# RasPiTimePowerSW_WithSTTS751.net
KiCad netlist of a schematic drawn in EAGLE
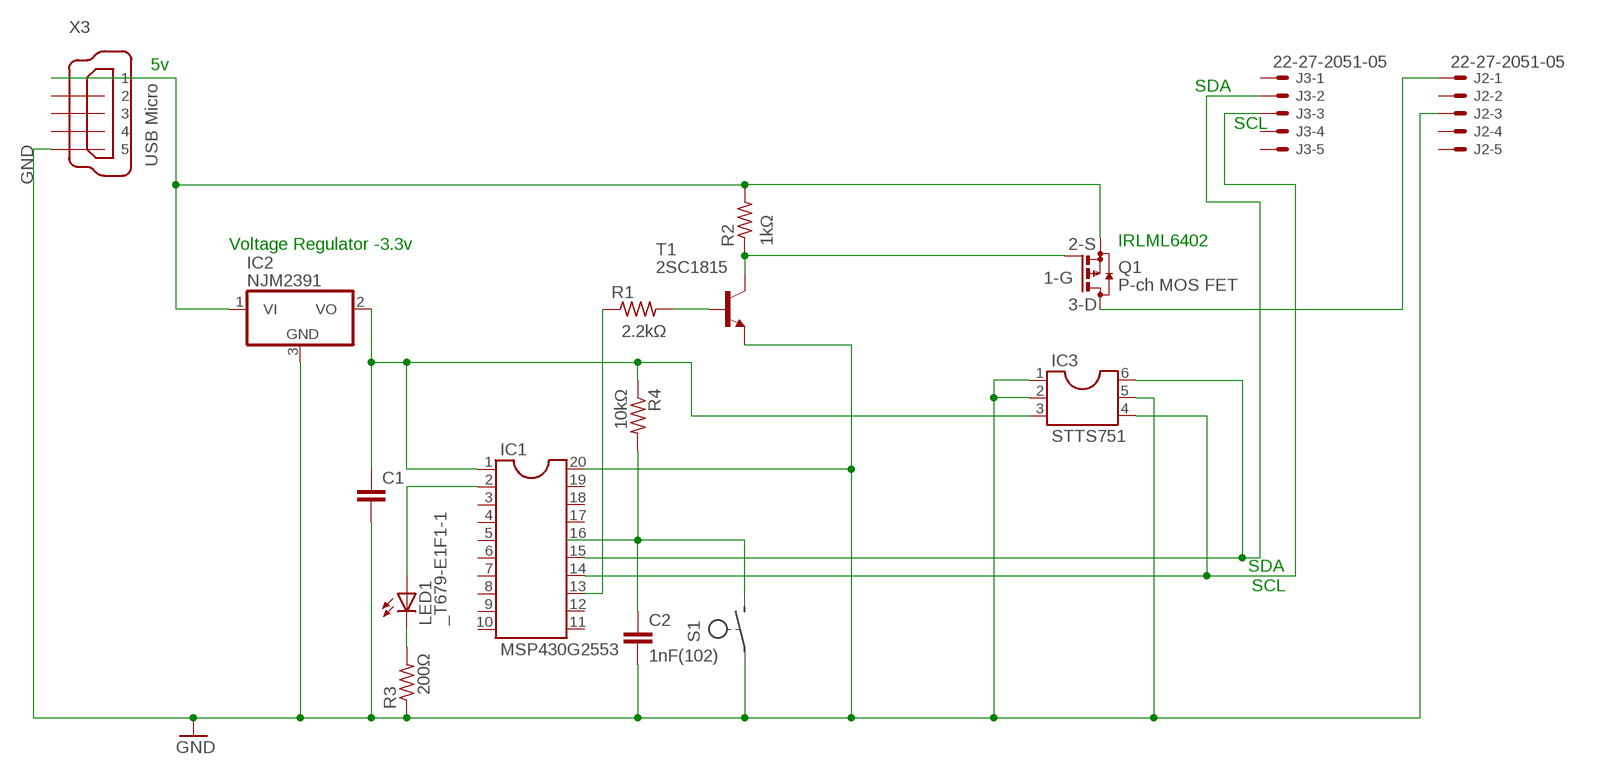
[diagram p0: schematic, sheet 1]

(export (version "E")
  (design (tool "Eeschema 10.0.6"))
  (components
    (comp (ref "C1")
      (value "C-EU075-042X103")
      (footprint "eagle-import:C075-042X103")
      (libsource (lib "eagle-import") (part "C-EU075-042X103"))
    )
    (comp (ref "C2")
      (value "1nF(102)")
      (footprint "eagle-import:C025-024X044")
      (libsource (lib "eagle-import") (part "C-EU025-024X044"))
    )
    (comp (ref "IC1")
      (value "MSP430G2553")
      (footprint "eagle-import:SOCKET-20")
      (libsource (lib "eagle-import") (part "DIL20S"))
    )
    (comp (ref "IC2")
      (value "NJM2391")
      (footprint "eagle-import:TO252")
      (libsource (lib "eagle-import") (part "78DT05"))
    )
    (comp (ref "IC3")
      (value "STTS751")
      (footprint "eagle-import:DIL06")
      (libsource (lib "eagle-import") (part "DIL6"))
    )
    (comp (ref "J2")
      (value "22-27-2051-05")
      (footprint "eagle-import:6410-05")
      (libsource (lib "eagle-import") (part "22-?-0527-2051"))
    )
    (comp (ref "J3")
      (value "22-27-2051-05")
      (footprint "eagle-import:6410-05")
      (libsource (lib "eagle-import") (part "22-?-0527-2051"))
    )
    (comp (ref "LED1")
      (value "_T679-E1F1-1")
      (footprint "eagle-import:PLCC2")
      (libsource (lib "eagle-import") (part "_T679-?-1E1F1LG"))
    )
    (comp (ref "Q1")
      (value "P-ch MOS FET")
      (footprint "eagle-import:SOT23")
      (libsource (lib "eagle-import") (part "BSS84"))
    )
    (comp (ref "R1")
      (value "R-US_M1206")
      (footprint "eagle-import:M1206")
      (fields (field (name "R") "2.2kΩ"))
      (libsource (lib "eagle-import") (part "R-US_M1206"))
    )
    (comp (ref "R2")
      (value "R-US_M1206")
      (footprint "eagle-import:M1206")
      (fields (field (name "1K") "1kΩ"))
      (libsource (lib "eagle-import") (part "R-US_M1206"))
    )
    (comp (ref "R3")
      (value "R-US_M1206")
      (footprint "eagle-import:M1206")
      (fields (field (name "R") "200Ω"))
      (libsource (lib "eagle-import") (part "R-US_M1206"))
    )
    (comp (ref "R4")
      (value "10kΩ")
      (footprint "eagle-import:M1206")
      (libsource (lib "eagle-import") (part "R-US_M1206"))
    )
    (comp (ref "T1")
      (value "2SC1815")
      (footprint "eagle-import:TO92-ECB")
      (libsource (lib "eagle-import") (part "2SC1815"))
    )
    (comp (ref "X3")
      (value "USB Micro")
      (footprint "eagle-import:32005-400")
      (libsource (lib "eagle-import") (part "MINI-USB_SHIELD5P4-32005-400"))
    )
  )
  (nets
    (net (code "1") (name "GND") (class "Default")
      (node (ref "C1") (pin "2") (pinfunction "2_2") (pintype "passive"))
      (node (ref "C2") (pin "2") (pinfunction "2_2") (pintype "passive"))
      (node (ref "IC1") (pin "20") (pinfunction "20_20") (pintype "passive"))
      (node (ref "IC2") (pin "3") (pinfunction "GND_3") (pintype "passive"))
      (node (ref "IC3") (pin "1") (pinfunction "1_1") (pintype "passive"))
      (node (ref "IC3") (pin "2") (pinfunction "2_2") (pintype "passive"))
      (node (ref "IC3") (pin "5") (pinfunction "5_5") (pintype "passive"))
      (node (ref "J2") (pin "3") (pinfunction "S_3") (pintype "passive"))
      (node (ref "R3") (pin "1") (pinfunction "1_1") (pintype "passive"))
      (node (ref "T1") (pin "E") (pinfunction "E_E") (pintype "passive"))
      (node (ref "X3") (pin "5") (pinfunction "5_5") (pintype "passive"))
    )
    (net (code "2") (name "Net-(C2-Pad1)") (class "Default")
      (node (ref "C2") (pin "1") (pinfunction "1_1") (pintype "passive"))
      (node (ref "R4") (pin "2") (pinfunction "2_2") (pintype "passive"))
    )
    (net (code "3") (name "Net-(IC1-Pad2)") (class "Default")
      (node (ref "IC1") (pin "2") (pinfunction "2_2") (pintype "passive"))
      (node (ref "LED1") (pin "A") (pinfunction "A_A") (pintype "passive"))
    )
    (net (code "4") (name "Net-(IC1-Pad13)") (class "Default")
      (node (ref "IC1") (pin "13") (pinfunction "13_13") (pintype "passive"))
      (node (ref "R1") (pin "1") (pinfunction "1_1") (pintype "passive"))
    )
    (net (code "5") (name "Net-(IC2-VI)") (class "Default")
      (node (ref "IC2") (pin "1") (pinfunction "VI_1") (pintype "input"))
      (node (ref "Q1") (pin "2") (pinfunction "S_2") (pintype "passive"))
      (node (ref "R2") (pin "2") (pinfunction "2_2") (pintype "passive"))
      (node (ref "X3") (pin "1") (pinfunction "1_1") (pintype "passive"))
    )
    (net (code "6") (name "Net-(IC2-VO)") (class "Default")
      (node (ref "C1") (pin "1") (pinfunction "1_1") (pintype "passive"))
      (node (ref "IC1") (pin "1") (pinfunction "1_1") (pintype "passive"))
      (node (ref "IC2") (pin "2") (pinfunction "VO_2") (pintype "passive"))
      (node (ref "IC3") (pin "3") (pinfunction "3_3") (pintype "passive"))
      (node (ref "R4") (pin "1") (pinfunction "1_1") (pintype "passive"))
    )
    (net (code "7") (name "Net-(J2A-S)") (class "Default")
      (node (ref "J2") (pin "1") (pinfunction "S_1") (pintype "passive"))
      (node (ref "Q1") (pin "3") (pinfunction "D_3") (pintype "passive"))
    )
    (net (code "8") (name "Net-(J3B-S)") (class "Default")
      (node (ref "IC1") (pin "15") (pinfunction "15_15") (pintype "passive"))
      (node (ref "IC3") (pin "6") (pinfunction "6_6") (pintype "passive"))
      (node (ref "J3") (pin "2") (pinfunction "S_2") (pintype "passive"))
    )
    (net (code "9") (name "Net-(J3C-S)") (class "Default")
      (node (ref "IC1") (pin "14") (pinfunction "14_14") (pintype "passive"))
      (node (ref "IC3") (pin "4") (pinfunction "4_4") (pintype "passive"))
      (node (ref "J3") (pin "3") (pinfunction "S_3") (pintype "passive"))
    )
    (net (code "10") (name "Net-(LED1-PadC)") (class "Default")
      (node (ref "LED1") (pin "C") (pinfunction "C_C") (pintype "passive"))
      (node (ref "R3") (pin "2") (pinfunction "2_2") (pintype "passive"))
    )
    (net (code "11") (name "Net-(Q1-G)") (class "Default")
      (node (ref "Q1") (pin "1") (pinfunction "G_1") (pintype "passive"))
      (node (ref "R2") (pin "1") (pinfunction "1_1") (pintype "passive"))
      (node (ref "T1") (pin "C") (pinfunction "C_C") (pintype "passive"))
    )
    (net (code "12") (name "Net-(R1-Pad2)") (class "Default")
      (node (ref "R1") (pin "2") (pinfunction "2_2") (pintype "passive"))
      (node (ref "T1") (pin "B") (pinfunction "B_B") (pintype "passive"))
    )
    (net (code "13") (name "unconnected-(IC1-Pad3)") (class "Default")
      (node (ref "IC1") (pin "3") (pinfunction "3_3") (pintype "passive"))
    )
    (net (code "14") (name "unconnected-(IC1-Pad4)") (class "Default")
      (node (ref "IC1") (pin "4") (pinfunction "4_4") (pintype "passive"))
    )
    (net (code "15") (name "unconnected-(IC1-Pad5)") (class "Default")
      (node (ref "IC1") (pin "5") (pinfunction "5_5") (pintype "passive"))
    )
    (net (code "16") (name "unconnected-(IC1-Pad6)") (class "Default")
      (node (ref "IC1") (pin "6") (pinfunction "6_6") (pintype "passive"))
    )
    (net (code "17") (name "unconnected-(IC1-Pad7)") (class "Default")
      (node (ref "IC1") (pin "7") (pinfunction "7_7") (pintype "passive"))
    )
    (net (code "18") (name "unconnected-(IC1-Pad8)") (class "Default")
      (node (ref "IC1") (pin "8") (pinfunction "8_8") (pintype "passive"))
    )
    (net (code "19") (name "unconnected-(IC1-Pad9)") (class "Default")
      (node (ref "IC1") (pin "9") (pinfunction "9_9") (pintype "passive"))
    )
    (net (code "20") (name "unconnected-(IC1-Pad10)") (class "Default")
      (node (ref "IC1") (pin "10") (pinfunction "10_10") (pintype "passive"))
    )
    (net (code "21") (name "unconnected-(IC1-Pad11)") (class "Default")
      (node (ref "IC1") (pin "11") (pinfunction "11_11") (pintype "passive"))
    )
    (net (code "22") (name "unconnected-(IC1-Pad12)") (class "Default")
      (node (ref "IC1") (pin "12") (pinfunction "12_12") (pintype "passive"))
    )
    (net (code "23") (name "unconnected-(IC1-Pad16)") (class "Default")
      (node (ref "IC1") (pin "16") (pinfunction "16_16") (pintype "passive"))
    )
    (net (code "24") (name "unconnected-(IC1-Pad17)") (class "Default")
      (node (ref "IC1") (pin "17") (pinfunction "17_17") (pintype "passive"))
    )
    (net (code "25") (name "unconnected-(IC1-Pad18)") (class "Default")
      (node (ref "IC1") (pin "18") (pinfunction "18_18") (pintype "passive"))
    )
    (net (code "26") (name "unconnected-(IC1-Pad19)") (class "Default")
      (node (ref "IC1") (pin "19") (pinfunction "19_19") (pintype "passive"))
    )
    (net (code "27") (name "unconnected-(J2B-S-Pad2)") (class "Default")
      (node (ref "J2") (pin "2") (pinfunction "S_2") (pintype "passive"))
    )
    (net (code "28") (name "unconnected-(J2D-S-Pad4)") (class "Default")
      (node (ref "J2") (pin "4") (pinfunction "S_4") (pintype "passive"))
    )
    (net (code "29") (name "unconnected-(J2E-S-Pad5)") (class "Default")
      (node (ref "J2") (pin "5") (pinfunction "S_5") (pintype "passive"))
    )
    (net (code "30") (name "unconnected-(J3A-S-Pad1)") (class "Default")
      (node (ref "J3") (pin "1") (pinfunction "S_1") (pintype "passive"))
    )
    (net (code "31") (name "unconnected-(J3D-S-Pad4)") (class "Default")
      (node (ref "J3") (pin "4") (pinfunction "S_4") (pintype "passive"))
    )
    (net (code "32") (name "unconnected-(J3E-S-Pad5)") (class "Default")
      (node (ref "J3") (pin "5") (pinfunction "S_5") (pintype "passive"))
    )
    (net (code "33") (name "unconnected-(X3-Pad2)") (class "Default")
      (node (ref "X3") (pin "2") (pinfunction "2_2") (pintype "passive"))
    )
    (net (code "34") (name "unconnected-(X3-Pad3)") (class "Default")
      (node (ref "X3") (pin "3") (pinfunction "3_3") (pintype "passive"))
    )
    (net (code "35") (name "unconnected-(X3-Pad4)") (class "Default")
      (node (ref "X3") (pin "4") (pinfunction "4_4") (pintype "passive"))
    )
  )
)
